# d11toy3.net
KiCad netlist of a schematic drawn in EAGLE
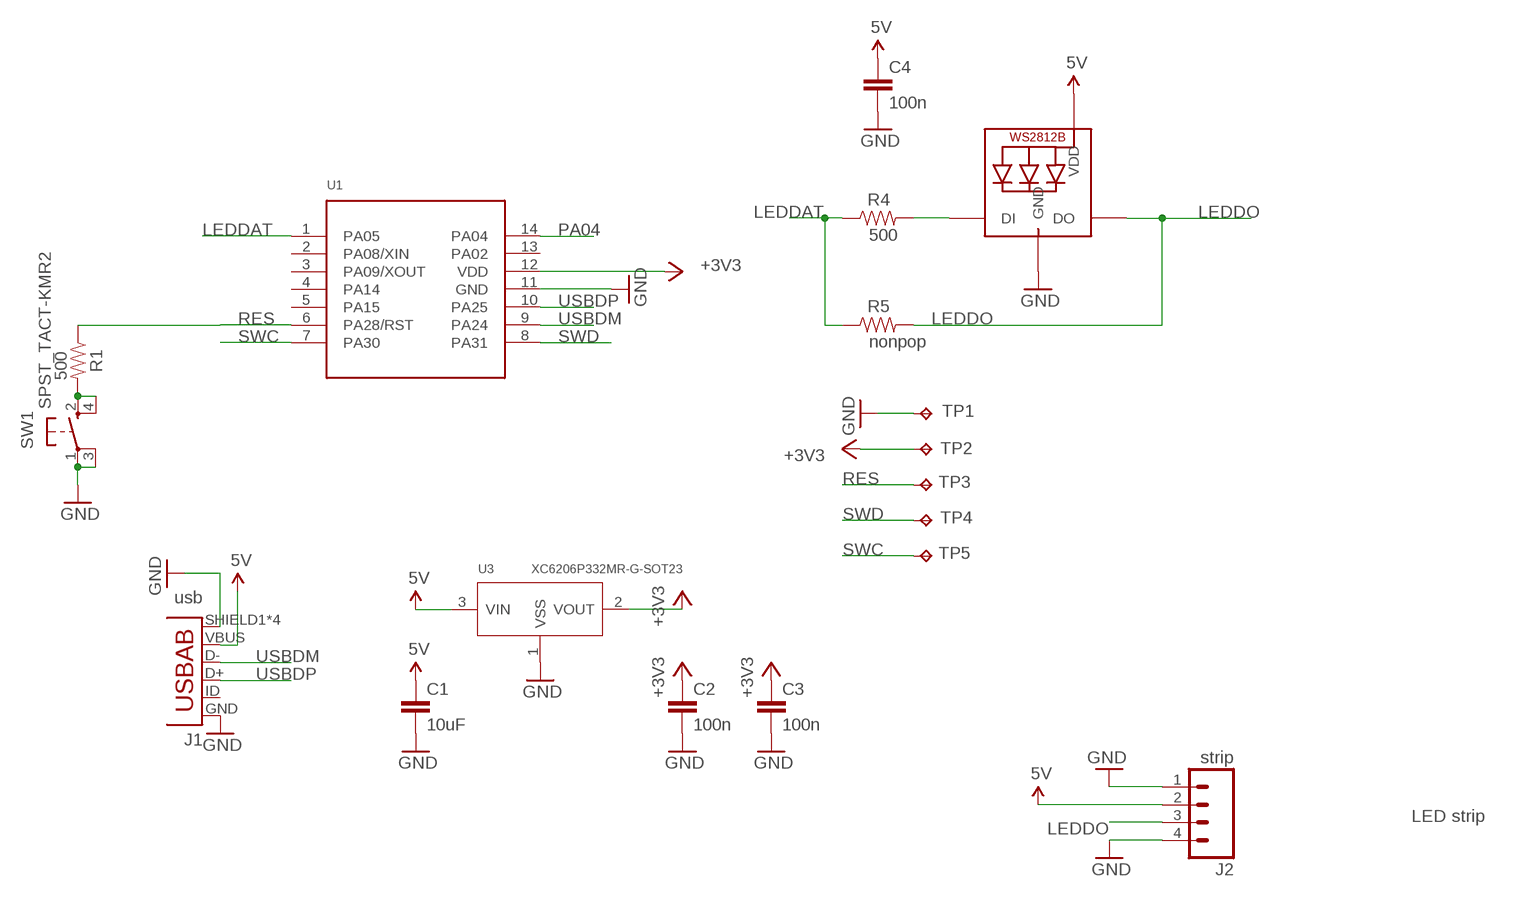
[diagram p0: schematic, sheet 1]

(export (version "E")
  (design (tool "Eeschema 10.0.6"))
  (components
    (comp (ref "C1")
      (value "10uF")
      (footprint "eagle-import:0603-CAP")
      (libsource (lib "eagle-import") (part "CAP0603-CAP"))
    )
    (comp (ref "C2")
      (value "100n")
      (footprint "eagle-import:0603-CAP")
      (libsource (lib "eagle-import") (part "CAP0603-CAP"))
    )
    (comp (ref "C3")
      (value "100n")
      (footprint "eagle-import:0603-CAP")
      (libsource (lib "eagle-import") (part "CAP0603-CAP"))
    )
    (comp (ref "C4")
      (value "100n")
      (footprint "eagle-import:0603-CAP")
      (libsource (lib "eagle-import") (part "CAP0603-CAP"))
    )
    (comp (ref "J1")
      (value "usb")
      (footprint "eagle-import:USB-AB-MICRO-SMD")
      (libsource (lib "eagle-import") (part "USB-AB"))
    )
    (comp (ref "J2")
      (value "strip")
      (footprint "eagle-import:1X04_NO_SILK_ALL_ROUND")
      (libsource (lib "eagle-import") (part "M04NO_SILK_ALL_ROUND"))
    )
    (comp (ref "LED2")
      (value "WS2812B5050")
      (footprint "eagle-import:WS2812B")
      (libsource (lib "eagle-import") (part "WS2812B5050"))
    )
    (comp (ref "R1")
      (value "500")
      (footprint "eagle-import:0603-RES")
      (libsource (lib "eagle-import") (part "RESISTOR0603-RES"))
    )
    (comp (ref "R4")
      (value "500")
      (footprint "eagle-import:0603-RES")
      (libsource (lib "eagle-import") (part "RESISTOR0603-RES"))
    )
    (comp (ref "R5")
      (value "nonpop")
      (footprint "eagle-import:0603-RES")
      (libsource (lib "eagle-import") (part "RESISTOR0603-RES"))
    )
    (comp (ref "SW1")
      (value "SPST_TACT-KMR2")
      (footprint "eagle-import:KMR2")
      (libsource (lib "eagle-import") (part "SPST_TACT-KMR2"))
    )
    (comp (ref "TP1")
      (value "TPB1,27")
      (footprint "eagle-import:B1,27")
      (libsource (lib "eagle-import") (part "TPB1,27"))
    )
    (comp (ref "TP2")
      (value "TPB1,27")
      (footprint "eagle-import:B1,27")
      (libsource (lib "eagle-import") (part "TPB1,27"))
    )
    (comp (ref "TP3")
      (value "TPB1,27")
      (footprint "eagle-import:B1,27")
      (libsource (lib "eagle-import") (part "TPB1,27"))
    )
    (comp (ref "TP4")
      (value "TPB1,27")
      (footprint "eagle-import:B1,27")
      (libsource (lib "eagle-import") (part "TPB1,27"))
    )
    (comp (ref "TP5")
      (value "TPB1,27")
      (footprint "eagle-import:B1,27")
      (libsource (lib "eagle-import") (part "TPB1,27"))
    )
    (comp (ref "U1")
      (value "SAMD11C14")
      (footprint "eagle-import:SO14")
      (libsource (lib "eagle-import") (part "SAMD11C14"))
    )
    (comp (ref "U3")
      (value "XC6206P332MR-G-SOT23")
      (footprint "eagle-import:SOT-23")
      (fields (field (name "MPN") "XC6206P332MR-G"))
      (libsource (lib "eagle-import") (part "PMIC-LDO-XC6206P332MR-G(SOT23)"))
    )
  )
  (nets
    (net (code "1") (name "+3V3") (class "Default")
      (node (ref "C2") (pin "1") (pinfunction "1_1") (pintype "passive"))
      (node (ref "C3") (pin "1") (pinfunction "1_1") (pintype "passive"))
      (node (ref "TP2") (pin "TP") (pinfunction "TP_TP") (pintype "input"))
      (node (ref "U1") (pin "12") (pinfunction "VDD_12") (pintype "bidirectional"))
      (node (ref "U3") (pin "2") (pinfunction "VOUT_2") (pintype "output"))
    )
    (net (code "2") (name "/LEDDAT") (class "Default")
      (node (ref "R4") (pin "1") (pinfunction "1_1") (pintype "passive"))
      (node (ref "R5") (pin "1") (pinfunction "1_1") (pintype "passive"))
      (node (ref "U1") (pin "1") (pinfunction "PA05_1") (pintype "bidirectional"))
    )
    (net (code "3") (name "/LEDDO") (class "Default")
      (node (ref "J2") (pin "3") (pinfunction "3_3") (pintype "passive"))
      (node (ref "LED2") (pin "2-DOUT") (pinfunction "DO_2-DOUT") (pintype "output"))
      (node (ref "R5") (pin "2") (pinfunction "2_2") (pintype "passive"))
    )
    (net (code "4") (name "/PA04") (class "Default")
      (node (ref "U1") (pin "14") (pinfunction "PA04_14") (pintype "bidirectional"))
    )
    (net (code "5") (name "/RES") (class "Default")
      (node (ref "R1") (pin "1") (pinfunction "1_1") (pintype "passive"))
      (node (ref "TP3") (pin "TP") (pinfunction "TP_TP") (pintype "input"))
      (node (ref "U1") (pin "6") (pinfunction "PA28/RST_6") (pintype "bidirectional"))
    )
    (net (code "6") (name "/SWC") (class "Default")
      (node (ref "TP5") (pin "TP") (pinfunction "TP_TP") (pintype "input"))
      (node (ref "U1") (pin "7") (pinfunction "PA30_7") (pintype "bidirectional"))
    )
    (net (code "7") (name "/SWD") (class "Default")
      (node (ref "TP4") (pin "TP") (pinfunction "TP_TP") (pintype "input"))
      (node (ref "U1") (pin "8") (pinfunction "PA31_8") (pintype "bidirectional"))
    )
    (net (code "8") (name "/USBDM") (class "Default")
      (node (ref "J1") (pin "D-") (pinfunction "D-_D-") (pintype "bidirectional"))
      (node (ref "U1") (pin "9") (pinfunction "PA24_9") (pintype "bidirectional"))
    )
    (net (code "9") (name "/USBDP") (class "Default")
      (node (ref "J1") (pin "D+") (pinfunction "D+_D+") (pintype "bidirectional"))
      (node (ref "U1") (pin "10") (pinfunction "PA25_10") (pintype "bidirectional"))
    )
    (net (code "10") (name "5V") (class "Default")
      (node (ref "C1") (pin "1") (pinfunction "1_1") (pintype "passive"))
      (node (ref "C4") (pin "1") (pinfunction "1_1") (pintype "passive"))
      (node (ref "J1") (pin "VBUS") (pinfunction "VBUS_VBUS") (pintype "bidirectional"))
      (node (ref "J2") (pin "2") (pinfunction "2_2") (pintype "passive"))
      (node (ref "LED2") (pin "1-VDD") (pinfunction "VDD_1-VDD") (pintype "power_in"))
      (node (ref "U3") (pin "3") (pinfunction "VIN_3") (pintype "input"))
    )
    (net (code "11") (name "GND") (class "Default")
      (node (ref "C1") (pin "2") (pinfunction "2_2") (pintype "passive"))
      (node (ref "C2") (pin "2") (pinfunction "2_2") (pintype "passive"))
      (node (ref "C3") (pin "2") (pinfunction "2_2") (pintype "passive"))
      (node (ref "C4") (pin "2") (pinfunction "2_2") (pintype "passive"))
      (node (ref "J1") (pin "GND") (pinfunction "GND_GND") (pintype "bidirectional"))
      (node (ref "J1") (pin "SHIELD1") (pinfunction "SHIELD_SHIELD1") (pintype "bidirectional"))
      (node (ref "J1") (pin "SHIELD2") (pinfunction "SHIELD_SHIELD2") (pintype "bidirectional"))
      (node (ref "J1") (pin "SHIELD3") (pinfunction "SHIELD_SHIELD3") (pintype "bidirectional"))
      (node (ref "J1") (pin "SHIELD4") (pinfunction "SHIELD_SHIELD4") (pintype "bidirectional"))
      (node (ref "J2") (pin "1") (pinfunction "1_1") (pintype "passive"))
      (node (ref "J2") (pin "4") (pinfunction "4_4") (pintype "passive"))
      (node (ref "LED2") (pin "3-GND") (pinfunction "GND_3-GND") (pintype "power_in"))
      (node (ref "SW1") (pin "1") (pinfunction "P_1") (pintype "passive"))
      (node (ref "SW1") (pin "3") (pinfunction "P1_3") (pintype "passive"))
      (node (ref "TP1") (pin "TP") (pinfunction "TP_TP") (pintype "input"))
      (node (ref "U1") (pin "11") (pinfunction "GND_11") (pintype "bidirectional"))
      (node (ref "U3") (pin "1") (pinfunction "VSS_1") (pintype "power_in"))
    )
    (net (code "12") (name "Net-(LED2-DI)") (class "Default")
      (node (ref "LED2") (pin "4-DIN") (pinfunction "DI_4-DIN") (pintype "input"))
      (node (ref "R4") (pin "2") (pinfunction "2_2") (pintype "passive"))
    )
    (net (code "13") (name "Net-(SW1-S)") (class "Default")
      (node (ref "R1") (pin "2") (pinfunction "2_2") (pintype "passive"))
      (node (ref "SW1") (pin "2") (pinfunction "S_2") (pintype "passive"))
      (node (ref "SW1") (pin "4") (pinfunction "S1_4") (pintype "passive"))
    )
    (net (code "14") (name "unconnected-(J1-USBID-PadID)") (class "Default")
      (node (ref "J1") (pin "ID") (pinfunction "USBID_ID") (pintype "bidirectional"))
    )
    (net (code "15") (name "unconnected-(U1-PA02-Pad13)") (class "Default")
      (node (ref "U1") (pin "13") (pinfunction "PA02_13") (pintype "bidirectional"))
    )
    (net (code "16") (name "unconnected-(U1-PA08{slash}XIN-Pad2)") (class "Default")
      (node (ref "U1") (pin "2") (pinfunction "PA08/XIN_2") (pintype "bidirectional"))
    )
    (net (code "17") (name "unconnected-(U1-PA09{slash}XOUT-Pad3)") (class "Default")
      (node (ref "U1") (pin "3") (pinfunction "PA09/XOUT_3") (pintype "bidirectional"))
    )
    (net (code "18") (name "unconnected-(U1-PA14-Pad4)") (class "Default")
      (node (ref "U1") (pin "4") (pinfunction "PA14_4") (pintype "bidirectional"))
    )
    (net (code "19") (name "unconnected-(U1-PA15-Pad5)") (class "Default")
      (node (ref "U1") (pin "5") (pinfunction "PA15_5") (pintype "bidirectional"))
    )
  )
)
